# Thermometer.net
KiCad netlist of a schematic drawn in Altium Designer
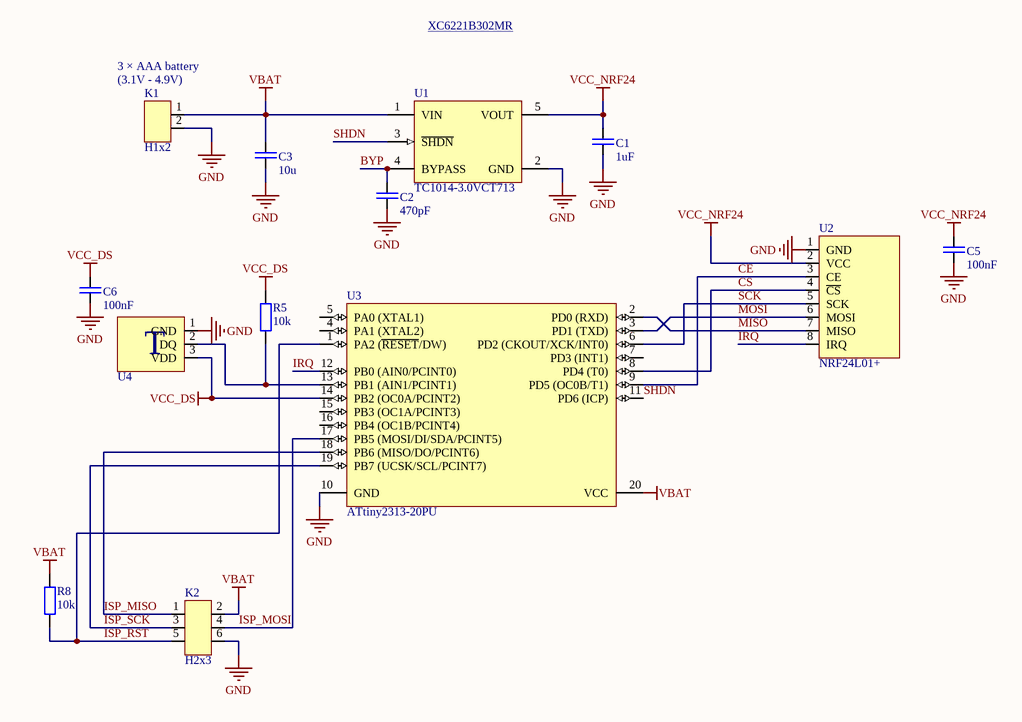
[diagram p0: Thermometer.SchDoc]

(export (version "E")
  (design (tool "Eeschema 10.0.6"))
  (components
    (comp (ref "C1")
      (value "1uF")
      (footprint "C2012_0805I_M")
      (description "Capacitor")
      (libsource (lib "General") (part "C"))
    )
    (comp (ref "C2")
      (value "470pF")
      (footprint "C2012_0805I_M")
      (description "Capacitor")
      (libsource (lib "General") (part "C"))
    )
    (comp (ref "C3")
      (value "10u")
      (footprint "C3225_1210I_M")
      (description "Capacitor")
      (libsource (lib "General") (part "C"))
    )
    (comp (ref "C5")
      (value "100nF")
      (footprint "C2012_0805I_M")
      (description "Capacitor")
      (libsource (lib "General") (part "C"))
    )
    (comp (ref "C6")
      (value "100nF")
      (footprint "C2012_0805I_M")
      (description "Capacitor")
      (libsource (lib "General") (part "C"))
    )
    (comp (ref "K1")
      (value "H1x2")
      (footprint "H1x2")
      (description "Header 1x2 (male)")
      (libsource (lib "Kon_Tipk") (part "H1x2"))
    )
    (comp (ref "K2")
      (value "H2x3")
      (footprint "H2x3")
      (description "Header 2x3 (male)")
      (libsource (lib "Kon_Tipk") (part "H2x3"))
    )
    (comp (ref "R5")
      (value "10k")
      (footprint "R2012_0805I_M")
      (description "R")
      (libsource (lib "General") (part "R"))
    )
    (comp (ref "R8")
      (value "10k")
      (footprint "R2012_0805I_M")
      (description "R")
      (libsource (lib "General") (part "R"))
    )
    (comp (ref "U1")
      (value "TC1014-3.0VCT713")
      (footprint "SOT-23-CT5_N")
      (fields (field (name "MANUFACTURER") "Microchip"))
      (libsource (lib "Microchip Power Management Line Regulator") (part "TC1014-3.0VCT713"))
    )
    (comp (ref "U2")
      (value "NRF24L01+")
      (footprint "NRF24L01+tht_module")
      (description "2.4GHz low power, long range module")
      (libsource (lib "Modules") (part "NRF24L01+"))
    )
    (comp (ref "U3")
      (value "ATtiny2313-20PU")
      (footprint "20P3")
      (libsource (lib "Atmel Microcontroller tinyAVR") (part "ATtiny2313-20PU"))
    )
    (comp (ref "U4")
      (value "DS18B20")
      (footprint "TO92")
      (description "Temperature sensor 1-wire interface")
      (libsource (lib "ICgeneral") (part "DS18B20"))
    )
  )
  (nets
    (net (code "1") (name "/BYP") (class "Default")
      (node (ref "C2") (pin "1") (pinfunction "1_1") (pintype "passive"))
      (node (ref "U1") (pin "4") (pinfunction "BYPASS_4") (pintype "passive"))
    )
    (net (code "2") (name "/CE") (class "Default")
      (node (ref "U2") (pin "3") (pinfunction "CE_3") (pintype "passive"))
      (node (ref "U3") (pin "9") (pinfunction "PD5_(OC0B/T1)_9") (pintype "bidirectional"))
    )
    (net (code "3") (name "/CS") (class "Default")
      (node (ref "U2") (pin "4") (pinfunction "~{CS}_4") (pintype "passive"))
      (node (ref "U3") (pin "8") (pinfunction "PD4_(T0)_8") (pintype "bidirectional"))
    )
    (net (code "4") (name "/IRQ") (class "Default")
      (node (ref "U2") (pin "8") (pinfunction "IRQ_8") (pintype "passive"))
      (node (ref "U3") (pin "12") (pinfunction "PB0_(AIN0/PCINT0)_12") (pintype "bidirectional"))
    )
    (net (code "5") (name "/ISP_MISO") (class "Default")
      (node (ref "K2") (pin "1") (pinfunction "1_1") (pintype "passive"))
      (node (ref "U3") (pin "18") (pinfunction "PB6_(MISO/DO/PCINT6)_18") (pintype "bidirectional"))
    )
    (net (code "6") (name "/ISP_MOSI") (class "Default")
      (node (ref "K2") (pin "4") (pinfunction "4_4") (pintype "passive"))
      (node (ref "U3") (pin "17") (pinfunction "PB5_(MOSI/DI/SDA/PCINT5)_17") (pintype "bidirectional"))
    )
    (net (code "7") (name "/ISP_RST") (class "Default")
      (node (ref "K2") (pin "5") (pinfunction "5_5") (pintype "passive"))
      (node (ref "R8") (pin "2") (pintype "passive"))
      (node (ref "U3") (pin "1") (pinfunction "PA2_(~{RESET}/DW)_1") (pintype "bidirectional"))
    )
    (net (code "8") (name "/ISP_SCK") (class "Default")
      (node (ref "K2") (pin "3") (pinfunction "3_3") (pintype "passive"))
      (node (ref "U3") (pin "19") (pinfunction "PB7_(UCSK/SCL/PCINT7)_19") (pintype "bidirectional"))
    )
    (net (code "9") (name "/MISO") (class "Default")
      (node (ref "U2") (pin "7") (pinfunction "MISO_7") (pintype "passive"))
      (node (ref "U3") (pin "2") (pinfunction "PD0_(RXD)_2") (pintype "bidirectional"))
    )
    (net (code "10") (name "/MOSI") (class "Default")
      (node (ref "U2") (pin "6") (pinfunction "MOSI_6") (pintype "passive"))
      (node (ref "U3") (pin "3") (pinfunction "PD1_(TXD)_3") (pintype "bidirectional"))
    )
    (net (code "11") (name "/SCK") (class "Default")
      (node (ref "U2") (pin "5") (pinfunction "SCK_5") (pintype "passive"))
      (node (ref "U3") (pin "6") (pinfunction "PD2_(CKOUT/XCK/INT0)_6") (pintype "bidirectional"))
    )
    (net (code "12") (name "/SHDN") (class "Default")
      (node (ref "U1") (pin "3") (pinfunction "~{SHDN}_3") (pintype "input"))
      (node (ref "U3") (pin "11") (pinfunction "PD6_(ICP)_11") (pintype "bidirectional"))
    )
    (net (code "13") (name "GND") (class "Default")
      (node (ref "C1") (pin "2") (pinfunction "2_2") (pintype "passive"))
      (node (ref "C2") (pin "2") (pinfunction "2_2") (pintype "passive"))
      (node (ref "C3") (pin "2") (pinfunction "2_2") (pintype "passive"))
      (node (ref "C5") (pin "2") (pinfunction "2_2") (pintype "passive"))
      (node (ref "C6") (pin "2") (pinfunction "2_2") (pintype "passive"))
      (node (ref "K1") (pin "2") (pinfunction "2_2") (pintype "passive"))
      (node (ref "K2") (pin "6") (pinfunction "6_6") (pintype "passive"))
      (node (ref "U1") (pin "2") (pinfunction "GND_2") (pintype "power_in"))
      (node (ref "U2") (pin "1") (pinfunction "GND_1") (pintype "passive"))
      (node (ref "U3") (pin "10") (pinfunction "GND_10") (pintype "power_in"))
      (node (ref "U4") (pin "1") (pinfunction "GND_1") (pintype "passive"))
    )
    (net (code "14") (name "Net-(U3-PB1_(AIN1{slash}PCINT1))") (class "Default")
      (node (ref "R5") (pin "2") (pintype "passive"))
      (node (ref "U3") (pin "13") (pinfunction "PB1_(AIN1/PCINT1)_13") (pintype "bidirectional"))
      (node (ref "U4") (pin "2") (pinfunction "DQ_2") (pintype "passive"))
    )
    (net (code "15") (name "VBAT") (class "Default")
      (node (ref "C3") (pin "1") (pinfunction "1_1") (pintype "passive"))
      (node (ref "K1") (pin "1") (pinfunction "1_1") (pintype "passive"))
      (node (ref "K2") (pin "2") (pinfunction "2_2") (pintype "passive"))
      (node (ref "R8") (pin "1") (pintype "passive"))
      (node (ref "U1") (pin "1") (pinfunction "VIN_1") (pintype "power_in"))
      (node (ref "U3") (pin "20") (pinfunction "VCC_20") (pintype "power_in"))
    )
    (net (code "16") (name "VCC_DS") (class "Default")
      (node (ref "C6") (pin "1") (pinfunction "1_1") (pintype "passive"))
      (node (ref "R5") (pin "1") (pintype "passive"))
      (node (ref "U3") (pin "14") (pinfunction "PB2_(OC0A/PCINT2)_14") (pintype "bidirectional"))
      (node (ref "U4") (pin "3") (pinfunction "VDD_3") (pintype "passive"))
    )
    (net (code "17") (name "VCC_NRF24") (class "Default")
      (node (ref "C1") (pin "1") (pinfunction "1_1") (pintype "passive"))
      (node (ref "C5") (pin "1") (pinfunction "1_1") (pintype "passive"))
      (node (ref "U1") (pin "5") (pinfunction "VOUT_5") (pintype "power_in"))
      (node (ref "U2") (pin "2") (pinfunction "VCC_2") (pintype "passive"))
    )
    (net (code "18") (name "unconnected-(U3-PA0_(XTAL1)-Pad5)") (class "Default")
      (node (ref "U3") (pin "5") (pinfunction "PA0_(XTAL1)_5") (pintype "bidirectional"))
    )
    (net (code "19") (name "unconnected-(U3-PA1_(XTAL2)-Pad4)") (class "Default")
      (node (ref "U3") (pin "4") (pinfunction "PA1_(XTAL2)_4") (pintype "bidirectional"))
    )
    (net (code "20") (name "unconnected-(U3-PB3_(OC1A{slash}PCINT3)-Pad15)") (class "Default")
      (node (ref "U3") (pin "15") (pinfunction "PB3_(OC1A/PCINT3)_15") (pintype "bidirectional"))
    )
    (net (code "21") (name "unconnected-(U3-PB4_(OC1B{slash}PCINT4)-Pad16)") (class "Default")
      (node (ref "U3") (pin "16") (pinfunction "PB4_(OC1B/PCINT4)_16") (pintype "bidirectional"))
    )
    (net (code "22") (name "unconnected-(U3-PD3_(INT1)-Pad7)") (class "Default")
      (node (ref "U3") (pin "7") (pinfunction "PD3_(INT1)_7") (pintype "bidirectional"))
    )
  )
)
